# flex_breakout.net
KiCad netlist of a schematic drawn in EAGLE
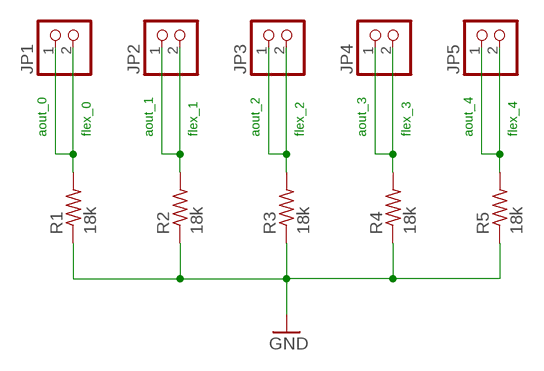
[diagram p0: schematic, sheet 1]

(export (version "E")
  (design (tool "Eeschema 10.0.6"))
  (components
    (comp (ref "JP1")
      (value "PINHD-1X2")
      (footprint "eagle-import:1X02")
      (libsource (lib "eagle-import") (part "PINHD-1X2"))
    )
    (comp (ref "JP2")
      (value "PINHD-1X2")
      (footprint "eagle-import:1X02")
      (libsource (lib "eagle-import") (part "PINHD-1X2"))
    )
    (comp (ref "JP3")
      (value "PINHD-1X2")
      (footprint "eagle-import:1X02")
      (libsource (lib "eagle-import") (part "PINHD-1X2"))
    )
    (comp (ref "JP4")
      (value "PINHD-1X2")
      (footprint "eagle-import:1X02")
      (libsource (lib "eagle-import") (part "PINHD-1X2"))
    )
    (comp (ref "JP5")
      (value "PINHD-1X2")
      (footprint "eagle-import:1X02")
      (libsource (lib "eagle-import") (part "PINHD-1X2"))
    )
    (comp (ref "R1")
      (value "18k")
      (footprint "eagle-import:0204_7")
      (libsource (lib "eagle-import") (part "R-US_0204/7"))
    )
    (comp (ref "R2")
      (value "18k")
      (footprint "eagle-import:0204_7")
      (libsource (lib "eagle-import") (part "R-US_0204/7"))
    )
    (comp (ref "R3")
      (value "18k")
      (footprint "eagle-import:0204_7")
      (libsource (lib "eagle-import") (part "R-US_0204/7"))
    )
    (comp (ref "R4")
      (value "18k")
      (footprint "eagle-import:0204_7")
      (libsource (lib "eagle-import") (part "R-US_0204/7"))
    )
    (comp (ref "R5")
      (value "18k")
      (footprint "eagle-import:0204_7")
      (libsource (lib "eagle-import") (part "R-US_0204/7"))
    )
  )
  (nets
    (net (code "1") (name "GND") (class "Default")
      (node (ref "R1") (pin "1") (pinfunction "1_1") (pintype "passive"))
      (node (ref "R2") (pin "1") (pinfunction "1_1") (pintype "passive"))
      (node (ref "R3") (pin "1") (pinfunction "1_1") (pintype "passive"))
      (node (ref "R4") (pin "1") (pinfunction "1_1") (pintype "passive"))
      (node (ref "R5") (pin "1") (pinfunction "1_1") (pintype "passive"))
    )
    (net (code "2") (name "Net-(JP1-Pad1)") (class "Default")
      (node (ref "JP1") (pin "1") (pinfunction "1_1") (pintype "passive"))
      (node (ref "JP1") (pin "2") (pinfunction "2_2") (pintype "passive"))
      (node (ref "R1") (pin "2") (pinfunction "2_2") (pintype "passive"))
    )
    (net (code "3") (name "Net-(JP2-Pad1)") (class "Default")
      (node (ref "JP2") (pin "1") (pinfunction "1_1") (pintype "passive"))
      (node (ref "JP2") (pin "2") (pinfunction "2_2") (pintype "passive"))
      (node (ref "R2") (pin "2") (pinfunction "2_2") (pintype "passive"))
    )
    (net (code "4") (name "Net-(JP3-Pad1)") (class "Default")
      (node (ref "JP3") (pin "1") (pinfunction "1_1") (pintype "passive"))
      (node (ref "JP3") (pin "2") (pinfunction "2_2") (pintype "passive"))
      (node (ref "R3") (pin "2") (pinfunction "2_2") (pintype "passive"))
    )
    (net (code "5") (name "Net-(JP4-Pad1)") (class "Default")
      (node (ref "JP4") (pin "1") (pinfunction "1_1") (pintype "passive"))
      (node (ref "JP4") (pin "2") (pinfunction "2_2") (pintype "passive"))
      (node (ref "R4") (pin "2") (pinfunction "2_2") (pintype "passive"))
    )
    (net (code "6") (name "Net-(JP5-Pad1)") (class "Default")
      (node (ref "JP5") (pin "1") (pinfunction "1_1") (pintype "passive"))
      (node (ref "JP5") (pin "2") (pinfunction "2_2") (pintype "passive"))
      (node (ref "R5") (pin "2") (pinfunction "2_2") (pintype "passive"))
    )
  )
)
